# CTH.net
KiCad netlist of a schematic drawn in EAGLE
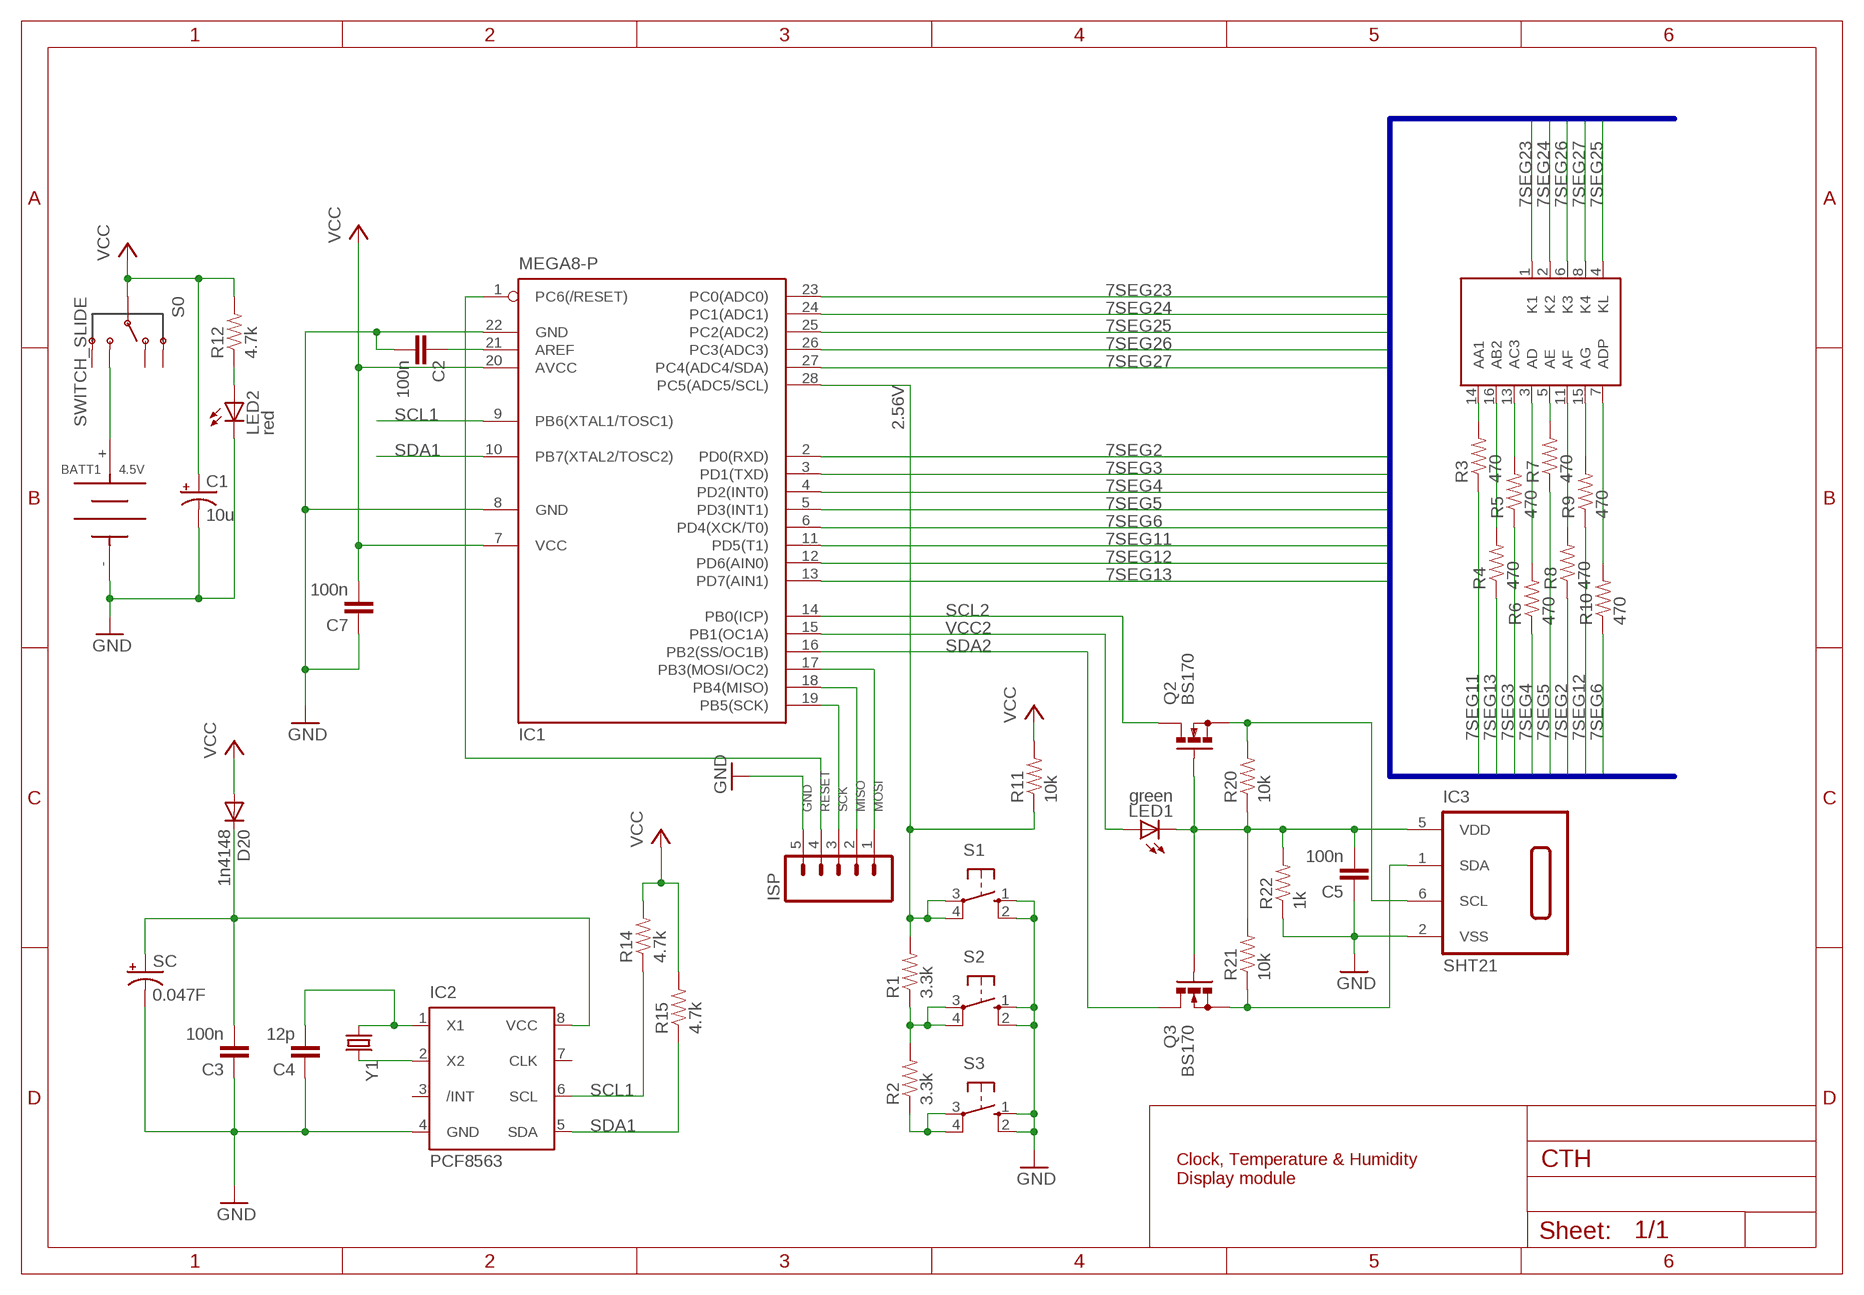
[diagram p0: schematic, sheet 1]

(export (version "E")
  (design (tool "Eeschema 10.0.6"))
  (components
    (comp (ref "7SEG")
      (value "LTC-4027JRLTC-4027JR")
      (footprint "eagle-import:LTC-4727JR")
      (libsource (lib "eagle-import") (part "LTC-4027JRLTC-4027JR"))
    )
    (comp (ref "BATT1")
      (value "1291-[2-56]")
      (footprint "eagle-import:1291")
      (libsource (lib "eagle-import") (part "1291-[2-56]"))
    )
    (comp (ref "C1")
      (value "10u")
      (footprint "eagle-import:CPOL-RADIAL-10UF-25V")
      (libsource (lib "eagle-import") (part "CAP_POLPTH2"))
    )
    (comp (ref "C2")
      (value "100n")
      (footprint "eagle-import:0805")
      (libsource (lib "eagle-import") (part "CAP0805"))
    )
    (comp (ref "C3")
      (value "100n")
      (footprint "eagle-import:0805")
      (libsource (lib "eagle-import") (part "CAP0805"))
    )
    (comp (ref "C4")
      (value "12p")
      (footprint "eagle-import:0805")
      (libsource (lib "eagle-import") (part "CAP0805"))
    )
    (comp (ref "C5")
      (value "100n")
      (footprint "eagle-import:0805")
      (libsource (lib "eagle-import") (part "CAP0805"))
    )
    (comp (ref "C7")
      (value "100n")
      (footprint "eagle-import:0805")
      (libsource (lib "eagle-import") (part "CAP0805"))
    )
    (comp (ref "D20")
      (value "1n4148")
      (footprint "eagle-import:SOD80C")
      (libsource (lib "eagle-import") (part "DIODE-SOD80C"))
    )
    (comp (ref "IC1")
      (value "MEGA8-P")
      (footprint "eagle-import:DIL28-3")
      (libsource (lib "eagle-import") (part "MEGA8-P"))
    )
    (comp (ref "IC2")
      (value "PCF8563")
      (footprint "eagle-import:DS1307_PCF8583_DIL08")
      (libsource (lib "eagle-import") (part "PCF8563"))
    )
    (comp (ref "IC3")
      (value "SHT21")
      (footprint "eagle-import:DFN6_SHT")
      (libsource (lib "eagle-import") (part "SHT21"))
    )
    (comp (ref "ISP")
      (value "M05PTH")
      (footprint "eagle-import:1X05")
      (libsource (lib "eagle-import") (part "M05PTH"))
    )
    (comp (ref "LED1")
      (value "green")
      (footprint "eagle-import:SPARKFUN_LED-1206")
      (libsource (lib "eagle-import") (part "SPARKFUN_LED1206"))
    )
    (comp (ref "LED2")
      (value "red")
      (footprint "eagle-import:LED3MM")
      (libsource (lib "eagle-import") (part "LED3MM"))
    )
    (comp (ref "Q2")
      (value "BS170")
      (footprint "eagle-import:SOT54E")
      (libsource (lib "eagle-import") (part "BS170"))
    )
    (comp (ref "Q3")
      (value "BS170")
      (footprint "eagle-import:SOT54E")
      (libsource (lib "eagle-import") (part "BS170"))
    )
    (comp (ref "R1")
      (value "3.3k")
      (footprint "eagle-import:0805")
      (libsource (lib "eagle-import") (part "RESISTOR0805-RES"))
    )
    (comp (ref "R2")
      (value "3.3k")
      (footprint "eagle-import:0805")
      (libsource (lib "eagle-import") (part "RESISTOR0805-RES"))
    )
    (comp (ref "R3")
      (value "470")
      (footprint "eagle-import:0805")
      (libsource (lib "eagle-import") (part "RESISTOR0805-RES"))
    )
    (comp (ref "R4")
      (value "470")
      (footprint "eagle-import:0805")
      (libsource (lib "eagle-import") (part "RESISTOR0805-RES"))
    )
    (comp (ref "R5")
      (value "470")
      (footprint "eagle-import:0805")
      (libsource (lib "eagle-import") (part "RESISTOR0805-RES"))
    )
    (comp (ref "R6")
      (value "470")
      (footprint "eagle-import:0805")
      (libsource (lib "eagle-import") (part "RESISTOR0805-RES"))
    )
    (comp (ref "R7")
      (value "470")
      (footprint "eagle-import:0805")
      (libsource (lib "eagle-import") (part "RESISTOR0805-RES"))
    )
    (comp (ref "R8")
      (value "470")
      (footprint "eagle-import:0805")
      (libsource (lib "eagle-import") (part "RESISTOR0805-RES"))
    )
    (comp (ref "R9")
      (value "470")
      (footprint "eagle-import:0805")
      (libsource (lib "eagle-import") (part "RESISTOR0805-RES"))
    )
    (comp (ref "R10")
      (value "470")
      (footprint "eagle-import:0805")
      (libsource (lib "eagle-import") (part "RESISTOR0805-RES"))
    )
    (comp (ref "R11")
      (value "10k")
      (footprint "eagle-import:0805")
      (libsource (lib "eagle-import") (part "RESISTOR0805-RES"))
    )
    (comp (ref "R12")
      (value "4.7k")
      (footprint "eagle-import:0805")
      (libsource (lib "eagle-import") (part "RESISTOR0805-RES"))
    )
    (comp (ref "R14")
      (value "4.7k")
      (footprint "eagle-import:0805")
      (libsource (lib "eagle-import") (part "RESISTOR0805-RES"))
    )
    (comp (ref "R15")
      (value "4.7k")
      (footprint "eagle-import:0805")
      (libsource (lib "eagle-import") (part "RESISTOR0805-RES"))
    )
    (comp (ref "R20")
      (value "10k")
      (footprint "eagle-import:0805")
      (libsource (lib "eagle-import") (part "RESISTOR0805-RES"))
    )
    (comp (ref "R21")
      (value "10k")
      (footprint "eagle-import:0805")
      (libsource (lib "eagle-import") (part "RESISTOR0805-RES"))
    )
    (comp (ref "R22")
      (value "1k")
      (footprint "eagle-import:0805")
      (libsource (lib "eagle-import") (part "RESISTOR0805-RES"))
    )
    (comp (ref "S0")
      (value "SWITCH_SLIDE")
      (footprint "eagle-import:SWITCH_SLIDE")
      (libsource (lib "eagle-import") (part "SWITCH_SLIDE"))
    )
    (comp (ref "S1")
      (value "10-XX")
      (footprint "eagle-import:B3F-10XX")
      (fields
        (field (name "MPN") "B3F-1000")
        (field (name "MPN_1") "B3F-1000")
        (field (name "OC_FARNELL") "176432")
        (field (name "OC_NEWARK") "36M3542")
      )
      (libsource (lib "eagle-import") (part "10-XX"))
    )
    (comp (ref "S2")
      (value "10-XX")
      (footprint "eagle-import:B3F-10XX")
      (fields (field (name "MPN") "B3F-1000"))
      (libsource (lib "eagle-import") (part "10-XX"))
    )
    (comp (ref "S3")
      (value "10-XX")
      (footprint "eagle-import:B3F-10XX")
      (fields (field (name "MPN") "B3F-1000"))
      (libsource (lib "eagle-import") (part "10-XX"))
    )
    (comp (ref "SC")
      (value "0.047F")
      (footprint "eagle-import:SUPERCAP_0.047F")
      (libsource (lib "eagle-import") (part "SUPERCAP_0.047F"))
    )
    (comp (ref "Y1")
      (value "CRYSTALTC38H")
      (footprint "eagle-import:TC38H")
      (libsource (lib "eagle-import") (part "CRYSTALTC38H"))
    )
  )
  (nets
    (net (code "1") (name "/2.56V") (class "Default")
      (node (ref "IC1") (pin "28") (pinfunction "PC5(ADC5/SCL)_28") (pintype "bidirectional"))
      (node (ref "R1") (pin "2") (pinfunction "2_2") (pintype "passive"))
      (node (ref "R11") (pin "1") (pinfunction "1_1") (pintype "passive"))
      (node (ref "S1") (pin "3") (pinfunction "P_3") (pintype "passive"))
      (node (ref "S1") (pin "4") (pinfunction "P1_4") (pintype "passive"))
    )
    (net (code "2") (name "/7SEG2") (class "Default")
      (node (ref "IC1") (pin "2") (pinfunction "PD0(RXD)_2") (pintype "bidirectional"))
      (node (ref "R8") (pin "1") (pinfunction "1_1") (pintype "passive"))
    )
    (net (code "3") (name "/7SEG3") (class "Default")
      (node (ref "IC1") (pin "3") (pinfunction "PD1(TXD)_3") (pintype "bidirectional"))
      (node (ref "R5") (pin "1") (pinfunction "1_1") (pintype "passive"))
    )
    (net (code "4") (name "/7SEG4") (class "Default")
      (node (ref "IC1") (pin "4") (pinfunction "PD2(INT0)_4") (pintype "bidirectional"))
      (node (ref "R6") (pin "1") (pinfunction "1_1") (pintype "passive"))
    )
    (net (code "5") (name "/7SEG5") (class "Default")
      (node (ref "IC1") (pin "5") (pinfunction "PD3(INT1)_5") (pintype "bidirectional"))
      (node (ref "R7") (pin "1") (pinfunction "1_1") (pintype "passive"))
    )
    (net (code "6") (name "/7SEG6") (class "Default")
      (node (ref "IC1") (pin "6") (pinfunction "PD4(XCK/T0)_6") (pintype "bidirectional"))
      (node (ref "R10") (pin "1") (pinfunction "1_1") (pintype "passive"))
    )
    (net (code "7") (name "/7SEG11") (class "Default")
      (node (ref "IC1") (pin "11") (pinfunction "PD5(T1)_11") (pintype "bidirectional"))
      (node (ref "R3") (pin "1") (pinfunction "1_1") (pintype "passive"))
    )
    (net (code "8") (name "/7SEG12") (class "Default")
      (node (ref "IC1") (pin "12") (pinfunction "PD6(AIN0)_12") (pintype "bidirectional"))
      (node (ref "R9") (pin "1") (pinfunction "1_1") (pintype "passive"))
    )
    (net (code "9") (name "/7SEG13") (class "Default")
      (node (ref "IC1") (pin "13") (pinfunction "PD7(AIN1)_13") (pintype "bidirectional"))
      (node (ref "R4") (pin "1") (pinfunction "1_1") (pintype "passive"))
    )
    (net (code "10") (name "/7SEG23") (class "Default")
      (node (ref "7SEG") (pin "1") (pinfunction "K1_1") (pintype "bidirectional"))
      (node (ref "IC1") (pin "23") (pinfunction "PC0(ADC0)_23") (pintype "bidirectional"))
    )
    (net (code "11") (name "/7SEG24") (class "Default")
      (node (ref "7SEG") (pin "2") (pinfunction "K2_2") (pintype "bidirectional"))
      (node (ref "IC1") (pin "24") (pinfunction "PC1(ADC1)_24") (pintype "bidirectional"))
    )
    (net (code "12") (name "/7SEG25") (class "Default")
      (node (ref "7SEG") (pin "4") (pinfunction "KL_4") (pintype "bidirectional"))
      (node (ref "IC1") (pin "25") (pinfunction "PC2(ADC2)_25") (pintype "bidirectional"))
    )
    (net (code "13") (name "/7SEG26") (class "Default")
      (node (ref "7SEG") (pin "6") (pinfunction "K3_6") (pintype "bidirectional"))
      (node (ref "IC1") (pin "26") (pinfunction "PC3(ADC3)_26") (pintype "bidirectional"))
    )
    (net (code "14") (name "/7SEG27") (class "Default")
      (node (ref "7SEG") (pin "8") (pinfunction "K4_8") (pintype "bidirectional"))
      (node (ref "IC1") (pin "27") (pinfunction "PC4(ADC4/SDA)_27") (pintype "bidirectional"))
    )
    (net (code "15") (name "/MISO") (class "Default")
      (node (ref "IC1") (pin "18") (pinfunction "PB4(MISO)_18") (pintype "bidirectional"))
      (node (ref "ISP") (pin "2") (pinfunction "2_2") (pintype "passive"))
    )
    (net (code "16") (name "/MOSI") (class "Default")
      (node (ref "IC1") (pin "17") (pinfunction "PB3(MOSI/OC2)_17") (pintype "bidirectional"))
      (node (ref "ISP") (pin "1") (pinfunction "1_1") (pintype "passive"))
    )
    (net (code "17") (name "/RESET") (class "Default")
      (node (ref "IC1") (pin "1") (pinfunction "PC6(/RESET)_1") (pintype "bidirectional"))
      (node (ref "ISP") (pin "4") (pinfunction "4_4") (pintype "passive"))
    )
    (net (code "18") (name "/SCK") (class "Default")
      (node (ref "IC1") (pin "19") (pinfunction "PB5(SCK)_19") (pintype "bidirectional"))
      (node (ref "ISP") (pin "3") (pinfunction "3_3") (pintype "passive"))
    )
    (net (code "19") (name "/SCL1") (class "Default")
      (node (ref "IC1") (pin "9") (pinfunction "PB6(XTAL1/TOSC1)_9") (pintype "bidirectional"))
      (node (ref "IC2") (pin "6") (pinfunction "SCL_6") (pintype "input"))
      (node (ref "R14") (pin "1") (pinfunction "1_1") (pintype "passive"))
    )
    (net (code "20") (name "/SCL2") (class "Default")
      (node (ref "IC1") (pin "14") (pinfunction "PB0(ICP)_14") (pintype "bidirectional"))
      (node (ref "Q2") (pin "D") (pinfunction "D_D") (pintype "passive"))
    )
    (net (code "21") (name "/SDA1") (class "Default")
      (node (ref "IC1") (pin "10") (pinfunction "PB7(XTAL2/TOSC2)_10") (pintype "bidirectional"))
      (node (ref "IC2") (pin "5") (pinfunction "SDA_5") (pintype "bidirectional"))
      (node (ref "R15") (pin "1") (pinfunction "1_1") (pintype "passive"))
    )
    (net (code "22") (name "/SDA2") (class "Default")
      (node (ref "IC1") (pin "16") (pinfunction "PB2(SS/OC1B)_16") (pintype "bidirectional"))
      (node (ref "Q3") (pin "D") (pinfunction "D_D") (pintype "passive"))
    )
    (net (code "23") (name "/VCC2") (class "Default")
      (node (ref "IC1") (pin "15") (pinfunction "PB1(OC1A)_15") (pintype "bidirectional"))
      (node (ref "LED1") (pin "A") (pinfunction "A_A") (pintype "passive"))
    )
    (net (code "24") (name "GND") (class "Default")
      (node (ref "BATT1") (pin "-") (pinfunction "-_-") (pintype "bidirectional"))
      (node (ref "C1") (pin "2") (pinfunction "-_2") (pintype "passive"))
      (node (ref "C2") (pin "2") (pinfunction "2_2") (pintype "passive"))
      (node (ref "C3") (pin "1") (pinfunction "1_1") (pintype "passive"))
      (node (ref "C4") (pin "1") (pinfunction "1_1") (pintype "passive"))
      (node (ref "C5") (pin "1") (pinfunction "1_1") (pintype "passive"))
      (node (ref "C7") (pin "1") (pinfunction "1_1") (pintype "passive"))
      (node (ref "IC1") (pin "22") (pinfunction "GND_22") (pintype "power_in"))
      (node (ref "IC1") (pin "8") (pinfunction "GND_8") (pintype "power_in"))
      (node (ref "IC2") (pin "4") (pinfunction "GND_4") (pintype "power_in"))
      (node (ref "IC3") (pin "2") (pinfunction "VSS_2") (pintype "power_in"))
      (node (ref "ISP") (pin "5") (pinfunction "5_5") (pintype "passive"))
      (node (ref "LED2") (pin "K") (pinfunction "C_K") (pintype "passive"))
      (node (ref "R22") (pin "1") (pinfunction "1_1") (pintype "passive"))
      (node (ref "S1") (pin "1") (pinfunction "S_1") (pintype "passive"))
      (node (ref "S1") (pin "2") (pinfunction "S1_2") (pintype "passive"))
      (node (ref "S2") (pin "1") (pinfunction "S_1") (pintype "passive"))
      (node (ref "S2") (pin "2") (pinfunction "S1_2") (pintype "passive"))
      (node (ref "S3") (pin "1") (pinfunction "S_1") (pintype "passive"))
      (node (ref "S3") (pin "2") (pinfunction "S1_2") (pintype "passive"))
      (node (ref "SC") (pin "2") (pinfunction "-_2") (pintype "passive"))
    )
    (net (code "25") (name "Net-(7SEG-AA1)") (class "Default")
      (node (ref "7SEG") (pin "14") (pinfunction "AA1_14") (pintype "bidirectional"))
      (node (ref "R3") (pin "2") (pinfunction "2_2") (pintype "passive"))
    )
    (net (code "26") (name "Net-(7SEG-AB2)") (class "Default")
      (node (ref "7SEG") (pin "16") (pinfunction "AB2_16") (pintype "bidirectional"))
      (node (ref "R4") (pin "2") (pinfunction "2_2") (pintype "passive"))
    )
    (net (code "27") (name "Net-(7SEG-AC3)") (class "Default")
      (node (ref "7SEG") (pin "13") (pinfunction "AC3_13") (pintype "bidirectional"))
      (node (ref "R5") (pin "2") (pinfunction "2_2") (pintype "passive"))
    )
    (net (code "28") (name "Net-(7SEG-AD)") (class "Default")
      (node (ref "7SEG") (pin "3") (pinfunction "AD_3") (pintype "bidirectional"))
      (node (ref "R6") (pin "2") (pinfunction "2_2") (pintype "passive"))
    )
    (net (code "29") (name "Net-(7SEG-ADP)") (class "Default")
      (node (ref "7SEG") (pin "7") (pinfunction "ADP_7") (pintype "bidirectional"))
      (node (ref "R10") (pin "2") (pinfunction "2_2") (pintype "passive"))
    )
    (net (code "30") (name "Net-(7SEG-AE)") (class "Default")
      (node (ref "7SEG") (pin "5") (pinfunction "AE_5") (pintype "bidirectional"))
      (node (ref "R7") (pin "2") (pinfunction "2_2") (pintype "passive"))
    )
    (net (code "31") (name "Net-(7SEG-AF)") (class "Default")
      (node (ref "7SEG") (pin "11") (pinfunction "AF_11") (pintype "bidirectional"))
      (node (ref "R8") (pin "2") (pinfunction "2_2") (pintype "passive"))
    )
    (net (code "32") (name "Net-(7SEG-AG)") (class "Default")
      (node (ref "7SEG") (pin "15") (pinfunction "AG_15") (pintype "bidirectional"))
      (node (ref "R9") (pin "2") (pinfunction "2_2") (pintype "passive"))
    )
    (net (code "33") (name "Net-(BATT1-Pad+)") (class "Default")
      (node (ref "BATT1") (pin "+") (pinfunction "+_+") (pintype "bidirectional"))
      (node (ref "S0") (pin "E") (pinfunction "E_E") (pintype "passive"))
    )
    (net (code "34") (name "Net-(IC1-AREF)") (class "Default")
      (node (ref "C2") (pin "1") (pinfunction "1_1") (pintype "passive"))
      (node (ref "IC1") (pin "21") (pinfunction "AREF_21") (pintype "passive"))
    )
    (net (code "35") (name "Net-(IC2-VCC)") (class "Default")
      (node (ref "C3") (pin "2") (pinfunction "2_2") (pintype "passive"))
      (node (ref "D20") (pin "C") (pinfunction "C_C") (pintype "passive"))
      (node (ref "IC2") (pin "8") (pinfunction "VCC_8") (pintype "power_in"))
      (node (ref "SC") (pin "1") (pinfunction "+_1") (pintype "passive"))
    )
    (net (code "36") (name "Net-(IC2-X1)") (class "Default")
      (node (ref "C4") (pin "2") (pinfunction "2_2") (pintype "passive"))
      (node (ref "IC2") (pin "1") (pinfunction "X1_1") (pintype "input"))
      (node (ref "Y1") (pin "1") (pinfunction "1_1") (pintype "passive"))
    )
    (net (code "37") (name "Net-(IC2-X2)") (class "Default")
      (node (ref "IC2") (pin "2") (pinfunction "X2_2") (pintype "output"))
      (node (ref "Y1") (pin "2") (pinfunction "2_2") (pintype "passive"))
    )
    (net (code "38") (name "Net-(IC3-SCL)") (class "Default")
      (node (ref "IC3") (pin "6") (pinfunction "SCL_6") (pintype "bidirectional"))
      (node (ref "Q2") (pin "S") (pinfunction "S_S") (pintype "passive"))
      (node (ref "R20") (pin "2") (pinfunction "2_2") (pintype "passive"))
    )
    (net (code "39") (name "Net-(IC3-SDA)") (class "Default")
      (node (ref "IC3") (pin "1") (pinfunction "SDA_1") (pintype "bidirectional"))
      (node (ref "Q3") (pin "S") (pinfunction "S_S") (pintype "passive"))
      (node (ref "R21") (pin "1") (pinfunction "1_1") (pintype "passive"))
    )
    (net (code "40") (name "Net-(IC3-VDD)") (class "Default")
      (node (ref "C5") (pin "2") (pinfunction "2_2") (pintype "passive"))
      (node (ref "IC3") (pin "5") (pinfunction "VDD_5") (pintype "power_in"))
      (node (ref "LED1") (pin "C") (pinfunction "C_C") (pintype "passive"))
      (node (ref "Q2") (pin "G") (pinfunction "G_G") (pintype "passive"))
      (node (ref "Q3") (pin "G") (pinfunction "G_G") (pintype "passive"))
      (node (ref "R20") (pin "1") (pinfunction "1_1") (pintype "passive"))
      (node (ref "R21") (pin "2") (pinfunction "2_2") (pintype "passive"))
      (node (ref "R22") (pin "2") (pinfunction "2_2") (pintype "passive"))
    )
    (net (code "41") (name "Net-(LED2-PadA)") (class "Default")
      (node (ref "LED2") (pin "A") (pinfunction "A_A") (pintype "passive"))
      (node (ref "R12") (pin "1") (pinfunction "1_1") (pintype "passive"))
    )
    (net (code "42") (name "Net-(S2-P)") (class "Default")
      (node (ref "R1") (pin "1") (pinfunction "1_1") (pintype "passive"))
      (node (ref "R2") (pin "2") (pinfunction "2_2") (pintype "passive"))
      (node (ref "S2") (pin "3") (pinfunction "P_3") (pintype "passive"))
      (node (ref "S2") (pin "4") (pinfunction "P1_4") (pintype "passive"))
    )
    (net (code "43") (name "Net-(S3-P)") (class "Default")
      (node (ref "R2") (pin "1") (pinfunction "1_1") (pintype "passive"))
      (node (ref "S3") (pin "3") (pinfunction "P_3") (pintype "passive"))
      (node (ref "S3") (pin "4") (pinfunction "P1_4") (pintype "passive"))
    )
    (net (code "44") (name "VCC") (class "Default")
      (node (ref "C1") (pin "1") (pinfunction "+_1") (pintype "passive"))
      (node (ref "C7") (pin "2") (pinfunction "2_2") (pintype "passive"))
      (node (ref "D20") (pin "A") (pinfunction "A_A") (pintype "passive"))
      (node (ref "IC1") (pin "20") (pinfunction "AVCC_20") (pintype "power_in"))
      (node (ref "IC1") (pin "7") (pinfunction "VCC_7") (pintype "power_in"))
      (node (ref "R11") (pin "2") (pinfunction "2_2") (pintype "passive"))
      (node (ref "R12") (pin "2") (pinfunction "2_2") (pintype "passive"))
      (node (ref "R14") (pin "2") (pinfunction "2_2") (pintype "passive"))
      (node (ref "R15") (pin "2") (pinfunction "2_2") (pintype "passive"))
      (node (ref "S0") (pin "M") (pinfunction "M_M") (pintype "passive"))
    )
    (net (code "45") (name "unconnected-(IC2-CLK-Pad7)") (class "Default")
      (node (ref "IC2") (pin "7") (pinfunction "CLK_7") (pintype "output"))
    )
    (net (code "46") (name "unconnected-(IC2-{slash}INT-Pad3)") (class "Default")
      (node (ref "IC2") (pin "3") (pinfunction "/INT_3") (pintype "input"))
    )
    (net (code "47") (name "unconnected-(S0-PadD)") (class "Default")
      (node (ref "S0") (pin "D") (pinfunction "D_D") (pintype "passive"))
    )
    (net (code "48") (name "unconnected-(S0-PadHOLD1)") (class "Default")
      (node (ref "S0") (pin "HOLD1") (pinfunction "HOLD1_HOLD1") (pintype "passive"))
    )
    (net (code "49") (name "unconnected-(S0-PadHOLD2)") (class "Default")
      (node (ref "S0") (pin "HOLD2") (pinfunction "HOLD2_HOLD2") (pintype "passive"))
    )
  )
)
